# MPR121-Cap-Touch-Keypad-v1_0.net
KiCad netlist of a schematic drawn in EAGLE
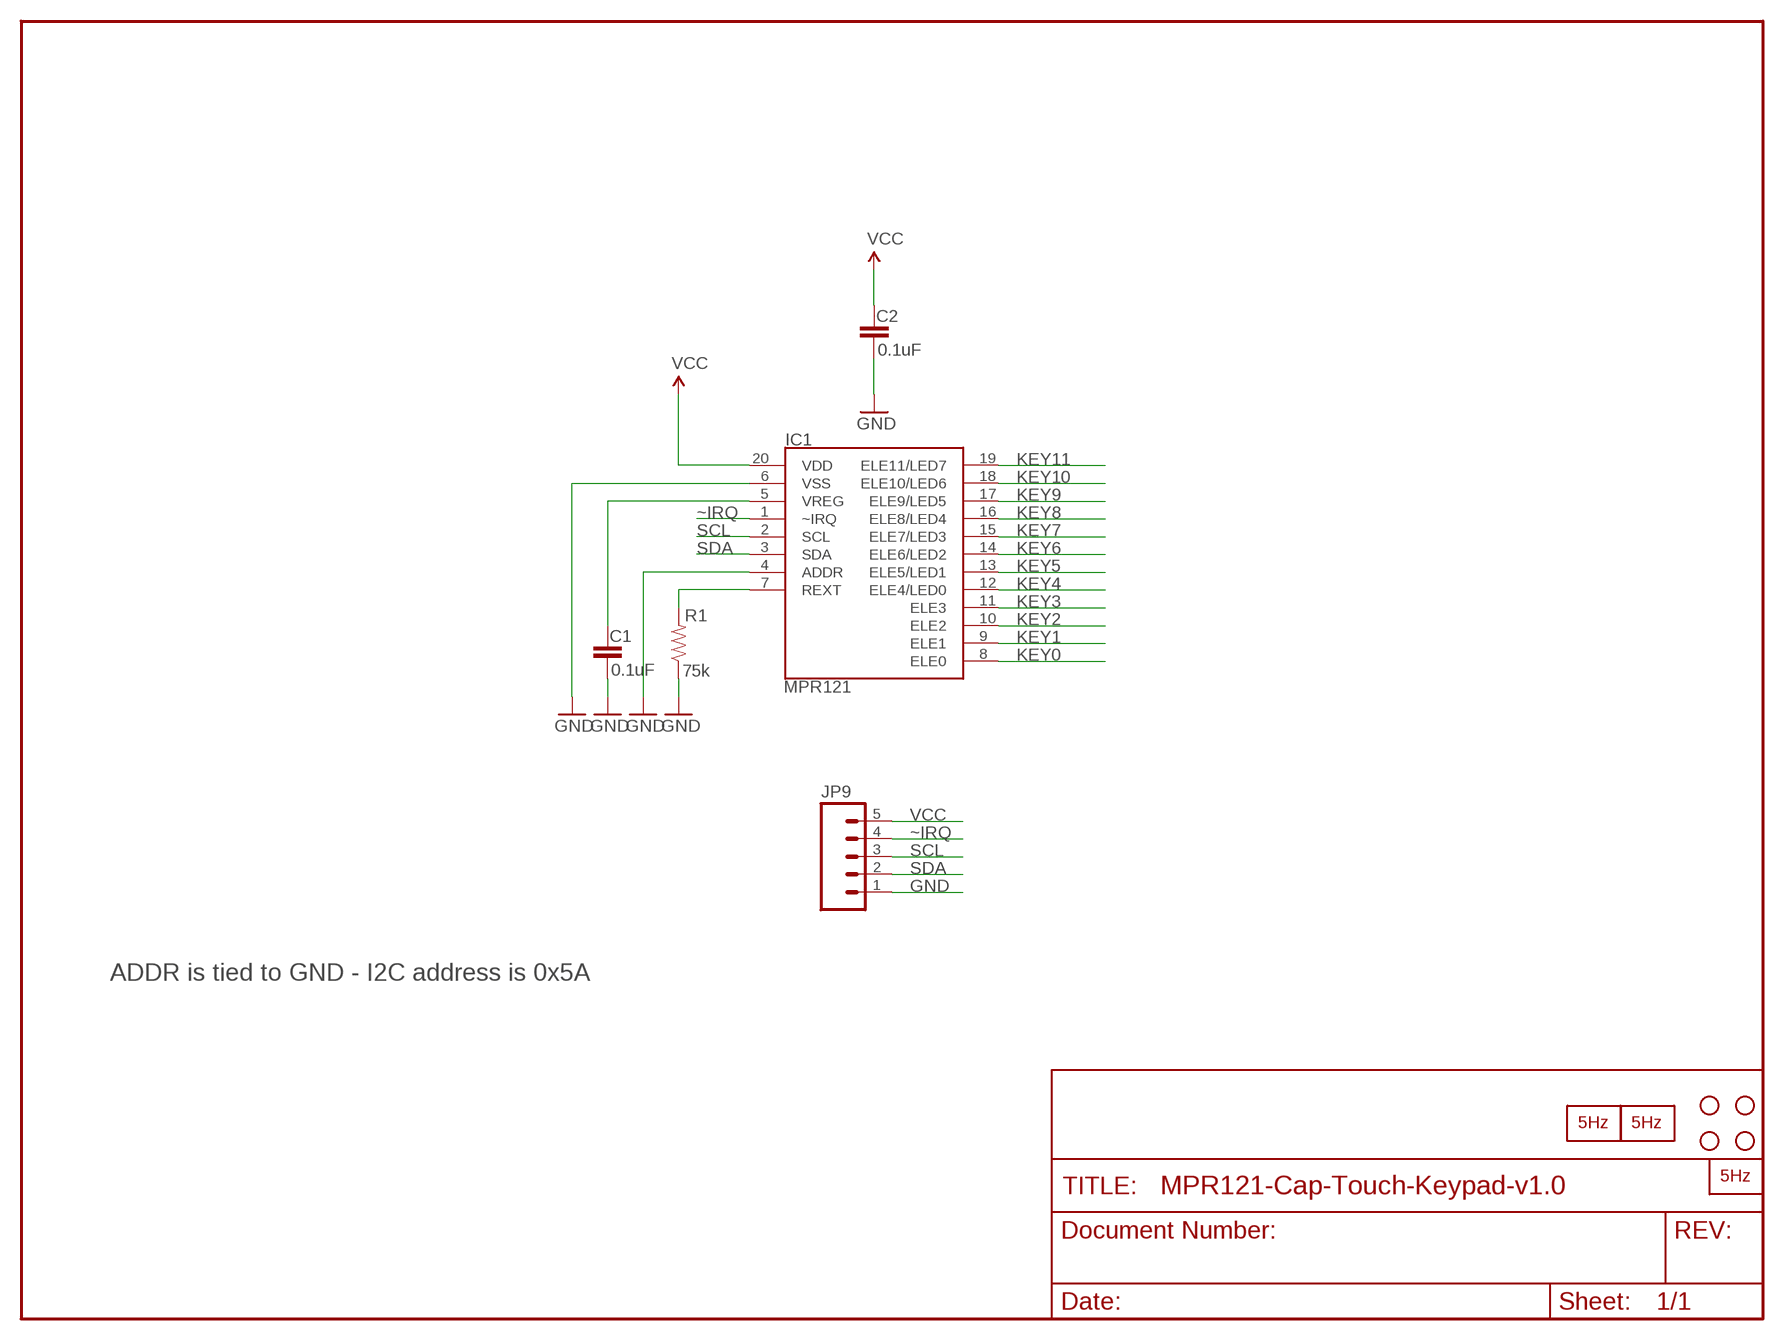
[diagram p0: schematic, sheet 1]

(export (version "E")
  (design (tool "Eeschema 10.0.6"))
  (components
    (comp (ref "C1")
      (value "0.1uF")
      (footprint "eagle-import:0402-CAP")
      (libsource (lib "eagle-import") (part "CAP0402-CAP"))
    )
    (comp (ref "C2")
      (value "0.1uF")
      (footprint "eagle-import:0402-CAP")
      (libsource (lib "eagle-import") (part "CAP0402-CAP"))
    )
    (comp (ref "IC1")
      (value "MPR121")
      (footprint "eagle-import:QFN-20-0.4MM")
      (libsource (lib "eagle-import") (part "MPR121QFN20"))
    )
    (comp (ref "JP3")
      (value "STAND-OFF")
      (footprint "eagle-import:STAND-OFF")
      (libsource (lib "eagle-import") (part "STAND-OFF"))
    )
    (comp (ref "JP4")
      (value "STAND-OFF")
      (footprint "eagle-import:STAND-OFF")
      (libsource (lib "eagle-import") (part "STAND-OFF"))
    )
    (comp (ref "JP7")
      (value "STAND-OFF")
      (footprint "eagle-import:STAND-OFF")
      (libsource (lib "eagle-import") (part "STAND-OFF"))
    )
    (comp (ref "JP8")
      (value "STAND-OFF")
      (footprint "eagle-import:STAND-OFF")
      (libsource (lib "eagle-import") (part "STAND-OFF"))
    )
    (comp (ref "JP9")
      (value "M05PTH")
      (footprint "eagle-import:1X05")
      (libsource (lib "eagle-import") (part "M05PTH"))
    )
    (comp (ref "R1")
      (value "75k")
      (footprint "eagle-import:0402-RES")
      (libsource (lib "eagle-import") (part "RESISTOR0402-RES"))
    )
    (comp (ref "U$1")
      (value "LOGO2_SILKL20MM")
      (footprint "eagle-import:LARGO2_20MM")
      (libsource (lib "eagle-import") (part "LOGO2_SILKL20MM"))
    )
    (comp (ref "U$2")
      (value "LOGO2_SILKC5MM")
      (footprint "eagle-import:CIRCULO2_5MM")
      (libsource (lib "eagle-import") (part "LOGO2_SILKC5MM"))
    )
    (comp (ref "U$3")
      (value "LOGO2_SILKC5MM")
      (footprint "eagle-import:CIRCULO2_5MM")
      (libsource (lib "eagle-import") (part "LOGO2_SILKC5MM"))
    )
  )
  (nets
    (net (code "1") (name "/KEY0") (class "Default")
      (node (ref "IC1") (pin "8") (pinfunction "ELE0_8") (pintype "bidirectional"))
    )
    (net (code "2") (name "/KEY1") (class "Default")
      (node (ref "IC1") (pin "9") (pinfunction "ELE1_9") (pintype "bidirectional"))
    )
    (net (code "3") (name "/KEY2") (class "Default")
      (node (ref "IC1") (pin "10") (pinfunction "ELE2_10") (pintype "bidirectional"))
    )
    (net (code "4") (name "/KEY3") (class "Default")
      (node (ref "IC1") (pin "11") (pinfunction "ELE3_11") (pintype "bidirectional"))
    )
    (net (code "5") (name "/KEY4") (class "Default")
      (node (ref "IC1") (pin "12") (pinfunction "ELE4/LED0_12") (pintype "bidirectional"))
    )
    (net (code "6") (name "/KEY5") (class "Default")
      (node (ref "IC1") (pin "13") (pinfunction "ELE5/LED1_13") (pintype "bidirectional"))
    )
    (net (code "7") (name "/KEY6") (class "Default")
      (node (ref "IC1") (pin "14") (pinfunction "ELE6/LED2_14") (pintype "bidirectional"))
    )
    (net (code "8") (name "/KEY7") (class "Default")
      (node (ref "IC1") (pin "15") (pinfunction "ELE7/LED3_15") (pintype "bidirectional"))
    )
    (net (code "9") (name "/KEY8") (class "Default")
      (node (ref "IC1") (pin "16") (pinfunction "ELE8/LED4_16") (pintype "bidirectional"))
    )
    (net (code "10") (name "/KEY9") (class "Default")
      (node (ref "IC1") (pin "17") (pinfunction "ELE9/LED5_17") (pintype "bidirectional"))
    )
    (net (code "11") (name "/KEY10") (class "Default")
      (node (ref "IC1") (pin "18") (pinfunction "ELE10/LED6_18") (pintype "bidirectional"))
    )
    (net (code "12") (name "/KEY11") (class "Default")
      (node (ref "IC1") (pin "19") (pinfunction "ELE11/LED7_19") (pintype "bidirectional"))
    )
    (net (code "13") (name "/SCL") (class "Default")
      (node (ref "IC1") (pin "2") (pinfunction "SCL_2") (pintype "bidirectional"))
      (node (ref "JP9") (pin "3") (pinfunction "3_3") (pintype "passive"))
    )
    (net (code "14") (name "/SDA") (class "Default")
      (node (ref "IC1") (pin "3") (pinfunction "SDA_3") (pintype "bidirectional"))
      (node (ref "JP9") (pin "2") (pinfunction "2_2") (pintype "passive"))
    )
    (net (code "15") (name "/~{IRQ}") (class "Default")
      (node (ref "IC1") (pin "1") (pinfunction "~{IRQ}_1") (pintype "bidirectional"))
      (node (ref "JP9") (pin "4") (pinfunction "4_4") (pintype "passive"))
    )
    (net (code "16") (name "GND") (class "Default")
      (node (ref "C1") (pin "2") (pinfunction "2_2") (pintype "passive"))
      (node (ref "C2") (pin "2") (pinfunction "2_2") (pintype "passive"))
      (node (ref "IC1") (pin "4") (pinfunction "ADDR_4") (pintype "bidirectional"))
      (node (ref "IC1") (pin "6") (pinfunction "VSS_6") (pintype "bidirectional"))
      (node (ref "JP9") (pin "1") (pinfunction "1_1") (pintype "passive"))
      (node (ref "R1") (pin "1") (pinfunction "1_1") (pintype "passive"))
    )
    (net (code "17") (name "Net-(IC1-REXT)") (class "Default")
      (node (ref "IC1") (pin "7") (pinfunction "REXT_7") (pintype "bidirectional"))
      (node (ref "R1") (pin "2") (pinfunction "2_2") (pintype "passive"))
    )
    (net (code "18") (name "Net-(IC1-VREG)") (class "Default")
      (node (ref "C1") (pin "1") (pinfunction "1_1") (pintype "passive"))
      (node (ref "IC1") (pin "5") (pinfunction "VREG_5") (pintype "bidirectional"))
    )
    (net (code "19") (name "VCC") (class "Default")
      (node (ref "C2") (pin "1") (pinfunction "1_1") (pintype "passive"))
      (node (ref "IC1") (pin "20") (pinfunction "VDD_20") (pintype "bidirectional"))
      (node (ref "JP9") (pin "5") (pinfunction "5_5") (pintype "passive"))
    )
  )
)
